# AIRZAI_BASE_BD_REVC_Sheet2.net
KiCad netlist of a schematic drawn in Altium Designer
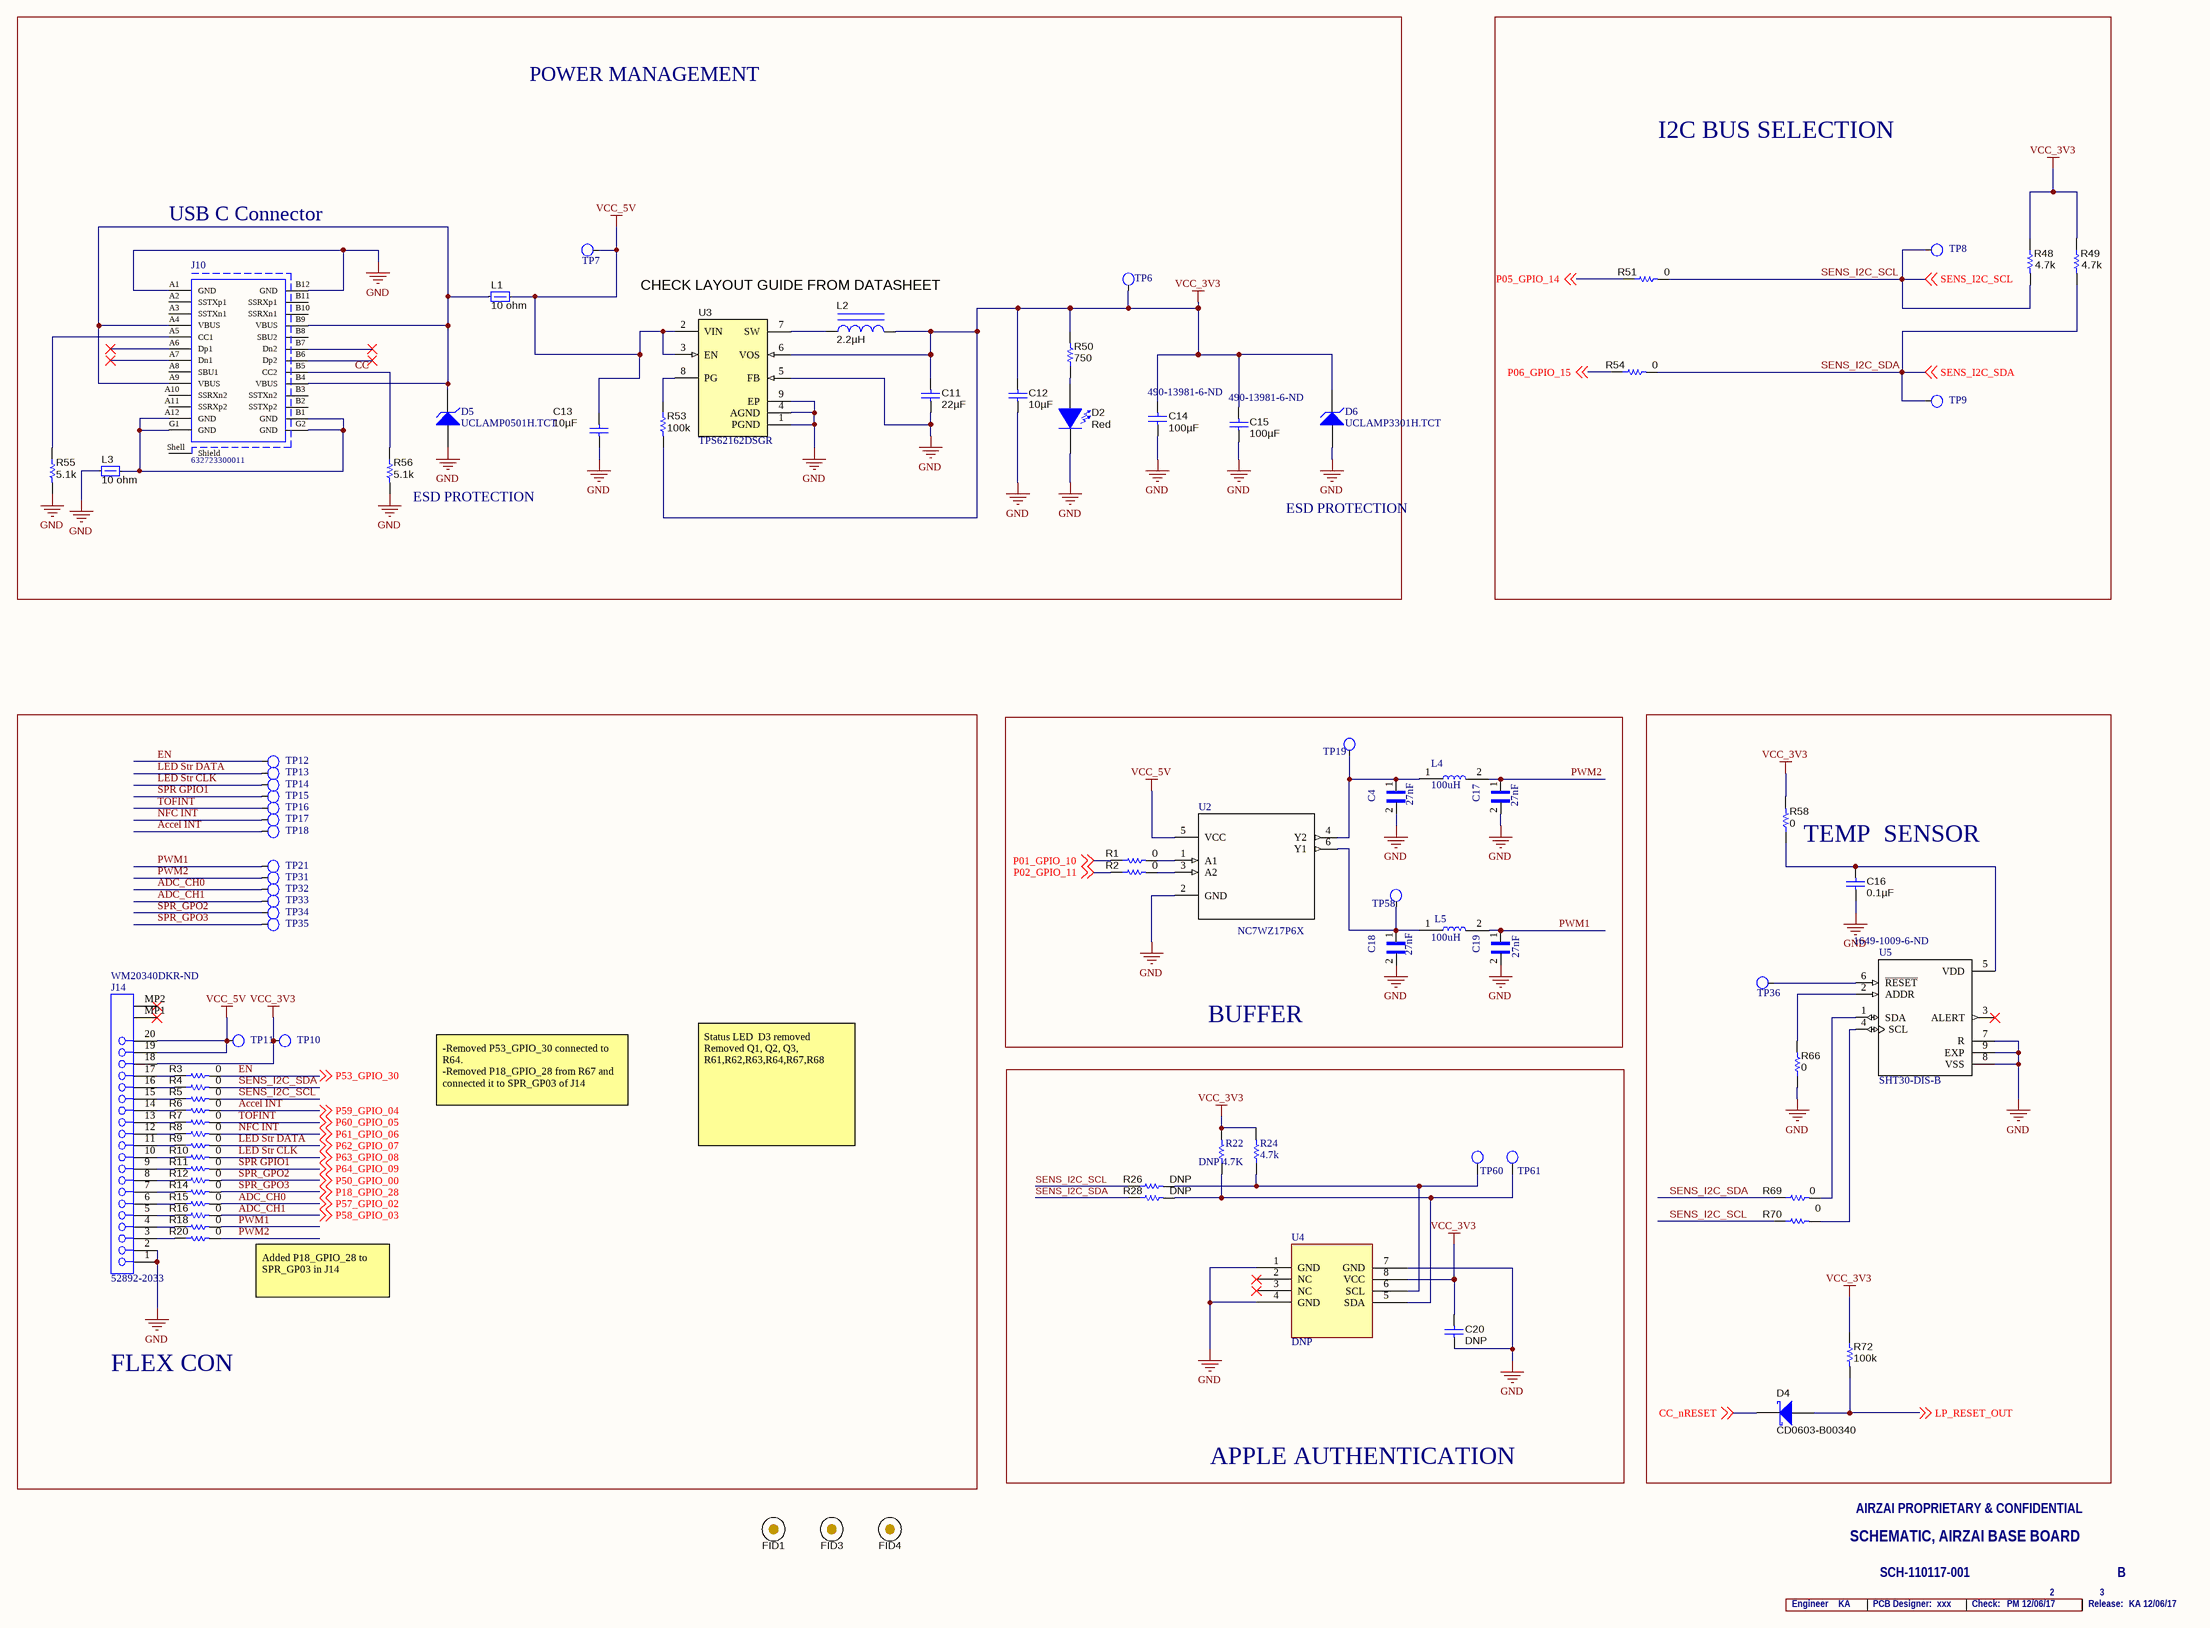
[diagram p0: AIRZAI_BASE_BD_REVC Sheet2.SchDoc]

(export (version "E")
  (design (tool "Eeschema 10.0.6"))
  (components
    (comp (ref "C4")
      (value "27nF")
      (footprint "1206CAP")
      (description "1206 27 nF 50 V Â±5% Tolerance C0G SMT Multilayer Ceramic Capacitor")
      (fields (field (name "MF") "Murata Electronics") (field (name "MP") "GRM3195C1H273JA01D"))
      (libsource (lib "GRM3195C1H273JA01D") (part "GRM3195C1H273JA01D"))
    )
    (comp (ref "C11")
      (value "C2012X5R1C226K125AC")
      (footprint "0805_HV")
      (description "CAP, CERM, 22 µF, 16 V, +/- 10%, X5R, 0805")
      (fields
        (field (name "VALUEDISPLAYED") "22µF")
        (field (name "MANUFACTURER") "TDK")
        (field (name "PUBLISHER") "Texas Instruments")
      )
      (libsource (lib "Capacitor_Ceramic") (part "C2012X5R1C226K125AC"))
    )
    (comp (ref "C12")
      (value "GRM21BR61A106KE19L")
      (footprint "0805_HV")
      (description "CAP, CERM, 10 µF, 10 V, +/- 10%, X5R, 0805")
      (fields
        (field (name "VALUEDISPLAYED") "10µF")
        (field (name "MANUFACTURER") "MuRata")
        (field (name "PUBLISHER") "Texas Instruments")
      )
      (libsource (lib "Capacitor_Ceramic") (part "GRM21BR61A106KE19L"))
    )
    (comp (ref "C13")
      (value "GRM21BR61A106KE19L")
      (footprint "0805_HV")
      (description "CAP, CERM, 10 µF, 10 V, +/- 10%, X5R, 0805")
      (fields
        (field (name "VALUEDISPLAYED") "10µF")
        (field (name "MANUFACTURER") "MuRata")
        (field (name "PUBLISHER") "Texas Instruments")
      )
      (libsource (lib "Capacitor_Ceramic") (part "GRM21BR61A106KE19L"))
    )
    (comp (ref "C14")
      (value "GRM31CR60J107ME39L")
      (footprint "1206_180")
      (description "CAP, CERM, 100 µF, 6.3 V, +/- 20%, X5R, 1206")
      (fields
        (field (name "VALUEDISPLAYED") "100µF")
        (field (name "MANUFACTURER") "MuRata")
        (field (name "SUPPLIER PART NUMBER 3") "490-13981-6-ND")
        (field (name "PUBLISHER") "Texas Instruments")
      )
      (libsource (lib "Capacitor_Ceramic") (part "GRM31CR60J107ME39L"))
    )
    (comp (ref "C15")
      (value "GRM31CR60J107ME39L")
      (footprint "1206_180")
      (description "CAP, CERM, 100 µF, 6.3 V, +/- 20%, X5R, 1206")
      (fields
        (field (name "VALUEDISPLAYED") "100µF")
        (field (name "MANUFACTURER") "MuRata")
        (field (name "SUPPLIER PART NUMBER 3") "490-13981-6-ND")
        (field (name "PUBLISHER") "Texas Instruments")
      )
      (libsource (lib "Capacitor_Ceramic") (part "GRM31CR60J107ME39L"))
    )
    (comp (ref "C16")
      (value "GRM155R61A104KA01D")
      (footprint "0402")
      (description "CAP, CERM, 0.1 µF, 10 V, +/- 10%, X5R, 0402")
      (fields
        (field (name "VALUEDISPLAYED") "0.1µF")
        (field (name "MANUFACTURER") "MuRata")
        (field (name "PUBLISHER") "Texas Instruments")
      )
      (libsource (lib "Capacitor_Ceramic") (part "GRM155R61A104KA01D"))
    )
    (comp (ref "C17")
      (value "27nF")
      (footprint "1206CAP")
      (description "1206 27 nF 50 V Â±5% Tolerance C0G SMT Multilayer Ceramic Capacitor")
      (fields (field (name "MF") "Murata Electronics") (field (name "MP") "GRM3195C1H273JA01D"))
      (libsource (lib "GRM3195C1H273JA01D") (part "GRM3195C1H273JA01D"))
    )
    (comp (ref "C18")
      (value "27nF")
      (footprint "1206CAP")
      (description "1206 27 nF 50 V Â±5% Tolerance C0G SMT Multilayer Ceramic Capacitor")
      (fields (field (name "MF") "Murata Electronics") (field (name "MP") "GRM3195C1H273JA01D"))
      (libsource (lib "GRM3195C1H273JA01D") (part "GRM3195C1H273JA01D"))
    )
    (comp (ref "C19")
      (value "27nF")
      (footprint "1206CAP")
      (description "1206 27 nF 50 V Â±5% Tolerance C0G SMT Multilayer Ceramic Capacitor")
      (fields (field (name "MF") "Murata Electronics") (field (name "MP") "GRM3195C1H273JA01D"))
      (libsource (lib "GRM3195C1H273JA01D") (part "GRM3195C1H273JA01D"))
    )
    (comp (ref "C20")
      (value "C1005X5R1A104K050BA")
      (footprint "SM0402_BTD.1SM_ACT_H55_CAP_WSS")
      (description "CAP, CERM, 0.1 µF, 10 V, +/- 10%, X5R, 0402")
      (fields
        (field (name "MANUFACTURER") "TDK")
        (field (name "VALUEDISPLAYED") "DNP")
        (field (name "PUBLISHER") "Texas Instruments")
      )
      (libsource (lib "AIRZAI_MBD_REVB2") (part "C1005X5R1A104K050BA"))
    )
    (comp (ref "D2")
      (value "Red")
      (footprint "SML-31_Red")
      (description "LED, Red, SMD")
      (fields
        (field (name "MANUFACTURER") "Rohm")
        (field (name "PARTNUMBER") "SML-311UTT86")
        (field (name "PUBLISHER") "Texas Instruments")
      )
      (libsource (lib "LED") (part "SML-311UTT86"))
    )
    (comp (ref "D4")
      (value "CD0603-B00340")
      (footprint "Diode_0603")
      (description "Diode, Schottky, 45 V, 0.03 A, 0603 Diode")
      (fields (field (name "MANUFACTURER") "Bourns") (field (name "PUBLISHER") "Texas Instruments"))
      (libsource (lib "Diode") (part "CD0603-B00340"))
    )
    (comp (ref "D5")
      (value "UCLAMP0501H.TCT")
      (footprint "SOD-523")
      (description "TVS DIODE 5V 12.5V SOD523")
      (fields (field (name "MANUFACTURER") "Semtech"))
      (libsource (lib "AIRZAI_BASE_BD_REVA") (part "UCLAMP0501H.TCT"))
    )
    (comp (ref "D6")
      (value "UCLAMP3301H.TCT")
      (footprint "SOD-523")
      (description "TVS DIODE 3.3V 8V SOD523")
      (fields (field (name "MANUFACTURER") "Semtech"))
      (libsource (lib "AIRZAI_BASE_BD_REVA") (part "UCLAMP3301H.TCT"))
    )
    (comp (ref "FID1")
      (value "Fiducial")
      (footprint "Fiducial10-20")
      (description "Fiducial mark.  There is nothing to buy or mount.")
      (fields (field (name "SYMBOLCREATOR") "codlsc") (field (name "PUBLISHER") "Texas Instruments"))
      (libsource (lib "MiscParts") (part "Fiducial"))
    )
    (comp (ref "FID3")
      (value "Fiducial")
      (footprint "Fiducial10-20")
      (description "Fiducial mark.  There is nothing to buy or mount.")
      (fields (field (name "SYMBOLCREATOR") "codlsc") (field (name "PUBLISHER") "Texas Instruments"))
      (libsource (lib "MiscParts") (part "Fiducial"))
    )
    (comp (ref "FID4")
      (value "Fiducial")
      (footprint "Fiducial10-20")
      (description "Fiducial mark.  There is nothing to buy or mount.")
      (fields (field (name "SYMBOLCREATOR") "codlsc") (field (name "PUBLISHER") "Texas Instruments"))
      (libsource (lib "MiscParts") (part "Fiducial"))
    )
    (comp (ref "J10")
      (value "632723300011")
      (footprint "632723300011")
      (description "USB 3.1 Type C Receptacle WR-COM, Horizontal, SMT / THT")
      (fields (field (name "PUBLISHER") "Wurth Elektronik"))
      (libsource (lib "Altium_WR-COM_USB-Connectors (rev18b)") (part "632723300011"))
    )
    (comp (ref "J14")
      (value "52892-2033")
      (footprint "MOLX-52892-2033")
      (fields (field (name "MANUFACTURER") "Molex") (field (name "SUPPLIER PART NUMBER 1") "WM20340DKR-ND"))
      (libsource (lib "Altium Content Vault") (part "MOLX-52892-2033"))
    )
    (comp (ref "L1")
      (value "10 ohm")
      (footprint "0402")
      (description "Ferrite Bead, 10 ohm @ 100 MHz, 1 A, 0402")
      (fields
        (field (name "PARTNUMBER") "BLM15AG100SN1D")
        (field (name "MANUFACTURER") "MuRata")
        (field (name "PUBLISHER") "Texas Instruments")
      )
      (libsource (lib "") (part "BLM15AG100SN1D_1"))
    )
    (comp (ref "L2")
      (value "BRC2012T2R2MD")
      (footprint "0805_HV")
      (description "Inductor, Wirewound, 2.2 µH, 1 A, 0.143 ohm, SMD")
      (fields
        (field (name "VALUEDISPLAYED") "2.2µH")
        (field (name "MANUFACTURER") "Taiyo Yuden")
        (field (name "PUBLISHER") "Texas Instruments")
      )
      (libsource (lib "Inductor_Other") (part "BRC2012T2R2MD"))
    )
    (comp (ref "L3")
      (value "10 ohm")
      (footprint "0402")
      (description "Ferrite Bead, 10 ohm @ 100 MHz, 1 A, 0402")
      (fields
        (field (name "PARTNUMBER") "BLM15AG100SN1D")
        (field (name "MANUFACTURER") "MuRata")
        (field (name "PUBLISHER") "Texas Instruments")
      )
      (libsource (lib "FerriteBead") (part "BLM15AG100SN1D"))
    )
    (comp (ref "L4")
      (value "100uH")
      (footprint "0805_Inductor")
      (description "Fixed Ind 100uh 2ma 3.1 Ohm Smd")
      (fields (field (name "MP") "MLF2012C101KTD25") (field (name "MF") "TDK"))
      (libsource (lib "MLF2012C101KTD25") (part "MLF2012C101KTD25"))
    )
    (comp (ref "L5")
      (value "100uH")
      (footprint "0805_Inductor")
      (description "Fixed Ind 100uh 2ma 3.1 Ohm Smd")
      (fields (field (name "MP") "MLF2012C101KTD25") (field (name "MF") "TDK"))
      (libsource (lib "MLF2012C101KTD25") (part "MLF2012C101KTD25"))
    )
    (comp (ref "R1")
      (value "ERJ-2GE0R00X")
      (footprint "0402")
      (description "RES, 0, 5%, 0.063 W, 0402")
      (fields
        (field (name "VALUEDISPLAYED") "0")
        (field (name "MANUFACTURER") "Panasonic")
        (field (name "DIGI-KEY_PART_NUMBER") "P0.0JCT-ND")
        (field (name "PUBLISHER") "Texas Instruments")
      )
      (libsource (lib "Resistor_0402") (part "ERJ-2GE0R00X"))
    )
    (comp (ref "R2")
      (value "ERJ-2GE0R00X")
      (footprint "0402")
      (description "RES, 0, 5%, 0.063 W, 0402")
      (fields
        (field (name "VALUEDISPLAYED") "0")
        (field (name "MANUFACTURER") "Panasonic")
        (field (name "DIGI-KEY_PART_NUMBER") "P0.0JCT-ND")
        (field (name "PUBLISHER") "Texas Instruments")
      )
      (libsource (lib "Resistor_0402") (part "ERJ-2GE0R00X"))
    )
    (comp (ref "R3")
      (value "ERJ-2GE0R00X")
      (footprint "0402")
      (description "RES, 0, 5%, 0.063 W, 0402")
      (fields
        (field (name "VALUEDISPLAYED") "0")
        (field (name "MANUFACTURER") "Panasonic")
        (field (name "PUBLISHER") "Texas Instruments")
      )
      (libsource (lib "Resistor_0402") (part "ERJ-2GE0R00X"))
    )
    (comp (ref "R4")
      (value "ERJ-2GE0R00X")
      (footprint "0402")
      (description "RES, 0, 5%, 0.063 W, 0402")
      (fields
        (field (name "VALUEDISPLAYED") "0")
        (field (name "MANUFACTURER") "Panasonic")
        (field (name "PUBLISHER") "Texas Instruments")
      )
      (libsource (lib "Resistor_0402") (part "ERJ-2GE0R00X"))
    )
    (comp (ref "R5")
      (value "ERJ-2GE0R00X")
      (footprint "0402")
      (description "RES, 0, 5%, 0.063 W, 0402")
      (fields
        (field (name "VALUEDISPLAYED") "0")
        (field (name "MANUFACTURER") "Panasonic")
        (field (name "PUBLISHER") "Texas Instruments")
      )
      (libsource (lib "Resistor_0402") (part "ERJ-2GE0R00X"))
    )
    (comp (ref "R6")
      (value "ERJ-2GE0R00X")
      (footprint "0402")
      (description "RES, 0, 5%, 0.063 W, 0402")
      (fields
        (field (name "VALUEDISPLAYED") "0")
        (field (name "MANUFACTURER") "Panasonic")
        (field (name "PUBLISHER") "Texas Instruments")
      )
      (libsource (lib "Resistor_0402") (part "ERJ-2GE0R00X"))
    )
    (comp (ref "R7")
      (value "ERJ-2GE0R00X")
      (footprint "0402")
      (description "RES, 0, 5%, 0.063 W, 0402")
      (fields
        (field (name "VALUEDISPLAYED") "0")
        (field (name "MANUFACTURER") "Panasonic")
        (field (name "PUBLISHER") "Texas Instruments")
      )
      (libsource (lib "Resistor_0402") (part "ERJ-2GE0R00X"))
    )
    (comp (ref "R8")
      (value "ERJ-2GE0R00X")
      (footprint "0402")
      (description "RES, 0, 5%, 0.063 W, 0402")
      (fields
        (field (name "VALUEDISPLAYED") "0")
        (field (name "MANUFACTURER") "Panasonic")
        (field (name "PUBLISHER") "Texas Instruments")
      )
      (libsource (lib "Resistor_0402") (part "ERJ-2GE0R00X"))
    )
    (comp (ref "R9")
      (value "ERJ-2GE0R00X")
      (footprint "0402")
      (description "RES, 0, 5%, 0.063 W, 0402")
      (fields
        (field (name "VALUEDISPLAYED") "0")
        (field (name "MANUFACTURER") "Panasonic")
        (field (name "PUBLISHER") "Texas Instruments")
      )
      (libsource (lib "Resistor_0402") (part "ERJ-2GE0R00X"))
    )
    (comp (ref "R10")
      (value "ERJ-2GE0R00X")
      (footprint "0402")
      (description "RES, 0, 5%, 0.063 W, 0402")
      (fields
        (field (name "VALUEDISPLAYED") "0")
        (field (name "MANUFACTURER") "Panasonic")
        (field (name "PUBLISHER") "Texas Instruments")
      )
      (libsource (lib "Resistor_0402") (part "ERJ-2GE0R00X"))
    )
    (comp (ref "R11")
      (value "ERJ-2GE0R00X")
      (footprint "0402")
      (description "RES, 0, 5%, 0.063 W, 0402")
      (fields
        (field (name "VALUEDISPLAYED") "0")
        (field (name "MANUFACTURER") "Panasonic")
        (field (name "PUBLISHER") "Texas Instruments")
      )
      (libsource (lib "Resistor_0402") (part "ERJ-2GE0R00X"))
    )
    (comp (ref "R12")
      (value "ERJ-2GE0R00X")
      (footprint "0402")
      (description "RES, 0, 5%, 0.063 W, 0402")
      (fields
        (field (name "VALUEDISPLAYED") "0")
        (field (name "MANUFACTURER") "Panasonic")
        (field (name "PUBLISHER") "Texas Instruments")
      )
      (libsource (lib "Resistor_0402") (part "ERJ-2GE0R00X"))
    )
    (comp (ref "R14")
      (value "ERJ-2GE0R00X")
      (footprint "0402")
      (description "RES, 0, 5%, 0.063 W, 0402")
      (fields
        (field (name "VALUEDISPLAYED") "0")
        (field (name "MANUFACTURER") "Panasonic")
        (field (name "PUBLISHER") "Texas Instruments")
      )
      (libsource (lib "Resistor_0402") (part "ERJ-2GE0R00X"))
    )
    (comp (ref "R15")
      (value "ERJ-2GE0R00X")
      (footprint "0402")
      (description "RES, 0, 5%, 0.063 W, 0402")
      (fields
        (field (name "VALUEDISPLAYED") "0")
        (field (name "MANUFACTURER") "Panasonic")
        (field (name "PUBLISHER") "Texas Instruments")
      )
      (libsource (lib "Resistor_0402") (part "ERJ-2GE0R00X"))
    )
    (comp (ref "R16")
      (value "ERJ-2GE0R00X")
      (footprint "0402")
      (description "RES, 0, 5%, 0.063 W, 0402")
      (fields
        (field (name "VALUEDISPLAYED") "0")
        (field (name "MANUFACTURER") "Panasonic")
        (field (name "PUBLISHER") "Texas Instruments")
      )
      (libsource (lib "Resistor_0402") (part "ERJ-2GE0R00X"))
    )
    (comp (ref "R18")
      (value "ERJ-2GE0R00X")
      (footprint "0402")
      (description "RES, 0, 5%, 0.063 W, 0402")
      (fields
        (field (name "VALUEDISPLAYED") "0")
        (field (name "MANUFACTURER") "Panasonic")
        (field (name "PUBLISHER") "Texas Instruments")
      )
      (libsource (lib "Resistor_0402") (part "ERJ-2GE0R00X"))
    )
    (comp (ref "R20")
      (value "ERJ-2GE0R00X")
      (footprint "0402")
      (description "RES, 0, 5%, 0.063 W, 0402")
      (fields
        (field (name "VALUEDISPLAYED") "0")
        (field (name "MANUFACTURER") "Panasonic")
        (field (name "PUBLISHER") "Texas Instruments")
      )
      (libsource (lib "Resistor_0402") (part "ERJ-2GE0R00X"))
    )
    (comp (ref "R22")
      (value "RMCF0402JT4K70")
      (footprint "0402")
      (description "Chip Resistor, 4.7 KOhm, +/- 5%, 0.063 W, -55 to 155 degC, 0402 (1005 Metric), RoHS, Tape and Reel")
      (fields
        (field (name "MANUFACTURER") "Stackpole-Electronics-Inc.")
        (field (name "TOLERANCE") "±5%")
        (field (name "RESISTANCE (OHMS)") "DNP 4.7K")
      )
      (libsource (lib "AIRZAI_BASE_BD_REVA") (part "RES-2"))
    )
    (comp (ref "R24")
      (value "RMCF0402JT4K70")
      (footprint "0402")
      (description "Chip Resistor, 4.7 KOhm, +/- 5%, 0.063 W, -55 to 155 degC, 0402 (1005 Metric), RoHS, Tape and Reel")
      (fields
        (field (name "MANUFACTURER") "Stackpole-Electronics-Inc.")
        (field (name "TOLERANCE") "±5%")
        (field (name "RESISTANCE (OHMS)") "4.7k")
      )
      (libsource (lib "AIRZAI_BASE_BD_REVA") (part "RES-2"))
    )
    (comp (ref "R26")
      (value "ERJ-2GE0R00X")
      (footprint "0402")
      (description "RES, 0, 5%, 0.063 W, 0402")
      (fields
        (field (name "VALUEDISPLAYED") "DNP")
        (field (name "MANUFACTURER") "Panasonic")
        (field (name "DIGI-KEY_PART_NUMBER") "P0.0JCT-ND")
        (field (name "PUBLISHER") "Texas Instruments")
      )
      (libsource (lib "Resistor_0402") (part "ERJ-2GE0R00X"))
    )
    (comp (ref "R28")
      (value "ERJ-2GE0R00X")
      (footprint "0402")
      (description "RES, 0, 5%, 0.063 W, 0402")
      (fields
        (field (name "VALUEDISPLAYED") "DNP")
        (field (name "MANUFACTURER") "Panasonic")
        (field (name "DIGI-KEY_PART_NUMBER") "P0.0JCT-ND")
        (field (name "PUBLISHER") "Texas Instruments")
      )
      (libsource (lib "Resistor_0402") (part "ERJ-2GE0R00X"))
    )
    (comp (ref "R48")
      (value "4.7k")
      (footprint "0402")
      (description "RES SMD 4.7K OHM 1% 1/16W 0402")
      (fields
        (field (name "MANUFACTURER") "Yageo")
        (field (name "MANUFACTURER PART NUMBER") "RC0402FR-074K7L")
      )
      (libsource (lib "Resistor_0402") (part "CRCW04023K30JNED"))
    )
    (comp (ref "R49")
      (value "4.7k")
      (footprint "0402")
      (description "RES SMD 4.7K OHM 1% 1/16W 0402")
      (fields
        (field (name "MANUFACTURER") "Yageo")
        (field (name "MANUFACTURER PART NUMBER") "RC0402FR-074K7L")
      )
      (libsource (lib "Resistor_0402") (part "CRCW04023K30JNED"))
    )
    (comp (ref "R50")
      (value "RC0603JR-07750RL")
      (footprint "0603")
      (description "RES, 750, 5%, 0.1 W, 0603")
      (fields
        (field (name "VALUEDISPLAYED") "750")
        (field (name "MANUFACTURER") "Yageo America")
        (field (name "PUBLISHER") "Texas Instruments")
      )
      (libsource (lib "Resistor_0603") (part "RC0603JR-07750RL"))
    )
    (comp (ref "R51")
      (value "ERJ-2GE0R00X")
      (footprint "0402")
      (description "RES, 0, 5%, 0.063 W, 0402")
      (fields
        (field (name "VALUEDISPLAYED") "0")
        (field (name "MANUFACTURER") "Panasonic")
        (field (name "PUBLISHER") "Texas Instruments")
      )
      (libsource (lib "Resistor_0402") (part "ERJ-2GE0R00X"))
    )
    (comp (ref "R53")
      (value "CRCW0402100KJNED")
      (footprint "0402")
      (description "RES, 100 k, 5%, 0.063 W, 0402")
      (fields
        (field (name "VALUEDISPLAYED") "100k")
        (field (name "MANUFACTURER") "Vishay-Dale")
        (field (name "PUBLISHER") "Texas Instruments")
      )
      (libsource (lib "Resistor_0402") (part "CRCW0402100KJNED"))
    )
    (comp (ref "R54")
      (value "ERJ-2GE0R00X")
      (footprint "0402")
      (description "RES, 0, 5%, 0.063 W, 0402")
      (fields
        (field (name "VALUEDISPLAYED") "0")
        (field (name "MANUFACTURER") "Panasonic")
        (field (name "PUBLISHER") "Texas Instruments")
      )
      (libsource (lib "Resistor_0402") (part "ERJ-2GE0R00X"))
    )
    (comp (ref "R55")
      (value "CRCW040210K0JNED")
      (footprint "0402")
      (description "RES, 10 k, 5%, 0.063 W, 0402")
      (fields
        (field (name "VALUEDISPLAYED") "5.1k")
        (field (name "MANUFACTURER") "Vishay-Dale")
        (field (name "PUBLISHER") "Texas Instruments")
      )
      (libsource (lib "Resistor_0402") (part "CRCW040210K0JNED"))
    )
    (comp (ref "R56")
      (value "CRCW040210K0JNED")
      (footprint "0402")
      (description "RES, 10 k, 5%, 0.063 W, 0402")
      (fields
        (field (name "VALUEDISPLAYED") "5.1k")
        (field (name "MANUFACTURER") "Vishay-Dale")
        (field (name "PUBLISHER") "Texas Instruments")
      )
      (libsource (lib "Resistor_0402") (part "CRCW040210K0JNED"))
    )
    (comp (ref "R58")
      (value "ERJ-2GE0R00X")
      (footprint "0402")
      (description "RES, 0, 5%, 0.063 W, 0402")
      (fields
        (field (name "VALUEDISPLAYED") "0")
        (field (name "MANUFACTURER") "Panasonic")
        (field (name "PUBLISHER") "Texas Instruments")
      )
      (libsource (lib "Resistor_0402") (part "ERJ-2GE0R00X"))
    )
    (comp (ref "R66")
      (value "ERJ-2GE0R00X")
      (footprint "0402")
      (description "RES, 0, 5%, 0.063 W, 0402")
      (fields
        (field (name "VALUEDISPLAYED") "0")
        (field (name "MANUFACTURER") "Panasonic")
        (field (name "PUBLISHER") "Texas Instruments")
      )
      (libsource (lib "Resistor_0402") (part "ERJ-2GE0R00X"))
    )
    (comp (ref "R69")
      (value "ERJ-2GE0R00X")
      (footprint "0402")
      (description "RES, 0, 5%, 0.063 W, 0402")
      (fields
        (field (name "VALUEDISPLAYED") "0")
        (field (name "MANUFACTURER") "Panasonic")
        (field (name "PUBLISHER") "Texas Instruments")
      )
      (libsource (lib "Resistor_0402") (part "ERJ-2GE0R00X"))
    )
    (comp (ref "R70")
      (value "ERJ-2GE0R00X")
      (footprint "0402")
      (description "RES, 0, 5%, 0.063 W, 0402")
      (fields
        (field (name "VALUEDISPLAYED") "0")
        (field (name "MANUFACTURER") "Panasonic")
        (field (name "PUBLISHER") "Texas Instruments")
      )
      (libsource (lib "Resistor_0402") (part "ERJ-2GE0R00X"))
    )
    (comp (ref "R72")
      (value "CRCW0402100KJNED")
      (footprint "0402")
      (description "RES, 100 k, 5%, 0.063 W, 0402")
      (fields
        (field (name "VALUEDISPLAYED") "100k")
        (field (name "MANUFACTURER") "Vishay-Dale")
        (field (name "PUBLISHER") "Texas Instruments")
      )
      (libsource (lib "Resistor_0402") (part "CRCW0402100KJNED"))
    )
    (comp (ref "TP6")
      (value "WIREPT")
      (footprint "TP_0.9MM")
      (libsource (lib "EAGLE_CAD_Library") (part "WIREPT"))
    )
    (comp (ref "TP7")
      (value "WIREPT")
      (footprint "TP_0.9MM")
      (libsource (lib "EAGLE_CAD_Library") (part "WIREPT"))
    )
    (comp (ref "TP8")
      (value "WIREPT")
      (footprint "TP_0.9MM")
      (libsource (lib "EAGLE_CAD_Library") (part "WIREPT"))
    )
    (comp (ref "TP9")
      (value "WIREPT")
      (footprint "TP_0.9MM")
      (libsource (lib "EAGLE_CAD_Library") (part "WIREPT"))
    )
    (comp (ref "TP10")
      (value "WIREPT")
      (footprint "TP_0.9MM")
      (libsource (lib "EAGLE_CAD_Library") (part "WIREPT"))
    )
    (comp (ref "TP11")
      (value "WIREPT")
      (footprint "TP_0.9MM")
      (libsource (lib "EAGLE_CAD_Library") (part "WIREPT"))
    )
    (comp (ref "TP12")
      (value "WIREPT")
      (footprint "TP_0.9MM")
      (libsource (lib "EAGLE_CAD_Library") (part "WIREPT"))
    )
    (comp (ref "TP13")
      (value "WIREPT")
      (footprint "TP_0.9MM")
      (libsource (lib "EAGLE_CAD_Library") (part "WIREPT"))
    )
    (comp (ref "TP14")
      (value "WIREPT")
      (footprint "TP_0.9MM")
      (libsource (lib "EAGLE_CAD_Library") (part "WIREPT"))
    )
    (comp (ref "TP15")
      (value "WIREPT")
      (footprint "TP_0.9MM")
      (libsource (lib "EAGLE_CAD_Library") (part "WIREPT"))
    )
    (comp (ref "TP16")
      (value "WIREPT")
      (footprint "TP_0.9MM")
      (libsource (lib "EAGLE_CAD_Library") (part "WIREPT"))
    )
    (comp (ref "TP17")
      (value "WIREPT")
      (footprint "TP_0.9MM")
      (libsource (lib "EAGLE_CAD_Library") (part "WIREPT"))
    )
    (comp (ref "TP18")
      (value "WIREPT")
      (footprint "TP_0.9MM")
      (libsource (lib "EAGLE_CAD_Library") (part "WIREPT"))
    )
    (comp (ref "TP19")
      (value "WIREPT")
      (footprint "TP_0.9MM")
      (libsource (lib "AIRZAI_MBD_REVB") (part "WIREPT"))
    )
    (comp (ref "TP21")
      (value "WIREPT")
      (footprint "TP_0.9MM")
      (libsource (lib "EAGLE_CAD_Library") (part "WIREPT"))
    )
    (comp (ref "TP31")
      (value "WIREPT")
      (footprint "TP_0.9MM")
      (libsource (lib "EAGLE_CAD_Library") (part "WIREPT"))
    )
    (comp (ref "TP32")
      (value "WIREPT")
      (footprint "TP_0.9MM")
      (libsource (lib "EAGLE_CAD_Library") (part "WIREPT"))
    )
    (comp (ref "TP33")
      (value "WIREPT")
      (footprint "TP_0.9MM")
      (libsource (lib "EAGLE_CAD_Library") (part "WIREPT"))
    )
    (comp (ref "TP34")
      (value "WIREPT")
      (footprint "TP_0.9MM")
      (libsource (lib "EAGLE_CAD_Library") (part "WIREPT"))
    )
    (comp (ref "TP35")
      (value "WIREPT")
      (footprint "TP_0.9MM")
      (libsource (lib "EAGLE_CAD_Library") (part "WIREPT"))
    )
    (comp (ref "TP36")
      (value "WIREPT")
      (footprint "TP_0.9MM")
      (libsource (lib "EAGLE_CAD_Library") (part "WIREPT"))
    )
    (comp (ref "TP58")
      (value "WIREPT")
      (footprint "TP_0.9MM")
      (libsource (lib "AIRZAI_MBD_REVB") (part "WIREPT"))
    )
    (comp (ref "TP60")
      (value "TESTPOINT")
      (footprint "TP_0.9MM")
      (libsource (lib "AIRZAI_LID_BD_REVA") (part "TESTPOINT"))
    )
    (comp (ref "TP61")
      (value "TESTPOINT")
      (footprint "TP_0.9MM")
      (libsource (lib "AIRZAI_LID_BD_REVA") (part "TESTPOINT"))
    )
    (comp (ref "U2")
      (value "NC7WZ17P6X")
      (footprint "SC-70-NC7WZ17P6X")
      (description "NC7WZ17 Series 5.5 V TinyLogic UHS Dual Buffer w/ Schmitt Trigger Inputs-SC-70-6")
      (fields (field (name "MF") "ON Semiconductor"))
      (libsource (lib "NC7WZ17P6X") (part "NC7WZ17P6X"))
    )
    (comp (ref "U3")
      (value "TPS62162DSGR")
      (footprint "DSG0008A")
      (fields
        (field (name "MANUFACTURER") "Texas Instruments")
        (field (name "ALTERNATE PARTNUMBER") "Equivalent")
      )
      (libsource (lib "TI Power Management Step-Down Regulator") (part "TPS62162DSGR"))
    )
    (comp (ref "U4")
      (value "DNP")
      (footprint "XDFN-8P-Apple")
      (description "Auth 3.0 CP")
      (fields (field (name "MP") "MFI343S00177") (field (name "MF") "Apple"))
      (libsource (lib "MFI337S3959") (part "Apple CP"))
    )
    (comp (ref "U5")
      (value "SHT30-DIS-B")
      (footprint "DFN250X250X100-9N")
      (description "SHT3x Series 5.5 V Â±3 %RH 0 to 100% Temperature and Humidity Sensor - DFN-8")
      (fields (field (name "MF") "Sensirion AG") (field (name "SUPPLIER PART NUMBER 1") "1649-1009-6-ND"))
      (libsource (lib "SHT30-DIS-B") (part "SHT30-DIS-B"))
    )
  )
  (nets
    (net (code "1") (name "/CC") (class "Default")
      (node (ref "J10") (pin "B5") (pinfunction "CC2_B5") (pintype "passive"))
      (node (ref "R56") (pin "1") (pinfunction "1_1") (pintype "passive"))
    )
    (net (code "2") (name "/PWM1") (class "Default")
      (node (ref "C19") (pin "1") (pinfunction "1_1") (pintype "passive"))
      (node (ref "L5") (pin "2") (pinfunction "2_2") (pintype "passive"))
      (node (ref "R18") (pin "2") (pinfunction "2_2") (pintype "passive"))
      (node (ref "TP21") (pin "1") (pinfunction "1_1") (pintype "passive"))
    )
    (net (code "3") (name "/PWM2") (class "Default")
      (node (ref "C17") (pin "1") (pinfunction "1_1") (pintype "passive"))
      (node (ref "L4") (pin "2") (pinfunction "2_2") (pintype "passive"))
      (node (ref "R20") (pin "2") (pinfunction "2_2") (pintype "passive"))
      (node (ref "TP31") (pin "1") (pinfunction "1_1") (pintype "passive"))
    )
    (net (code "4") (name "CC_nRESET") (class "Default")
      (node (ref "D4") (pin "1") (pinfunction "K_1") (pintype "passive"))
    )
    (net (code "5") (name "GND") (class "Default")
      (node (ref "C11") (pin "2") (pinfunction "2_2") (pintype "passive"))
      (node (ref "C12") (pin "2") (pinfunction "2_2") (pintype "passive"))
      (node (ref "C13") (pin "2") (pinfunction "2_2") (pintype "passive"))
      (node (ref "C14") (pin "2") (pinfunction "2_2") (pintype "passive"))
      (node (ref "C15") (pin "2") (pinfunction "2_2") (pintype "passive"))
      (node (ref "C16") (pin "2") (pinfunction "2_2") (pintype "passive"))
      (node (ref "C17") (pin "2") (pinfunction "2_2") (pintype "passive"))
      (node (ref "C18") (pin "2") (pinfunction "2_2") (pintype "passive"))
      (node (ref "C19") (pin "2") (pinfunction "2_2") (pintype "passive"))
      (node (ref "C20") (pin "2") (pinfunction "2_2") (pintype "passive"))
      (node (ref "C4") (pin "2") (pinfunction "2_2") (pintype "passive"))
      (node (ref "D2") (pin "1") (pinfunction "K_1") (pintype "passive"))
      (node (ref "D5") (pin "A") (pinfunction "A_A") (pintype "passive"))
      (node (ref "D6") (pin "A") (pinfunction "A_A") (pintype "passive"))
      (node (ref "J10") (pin "A1") (pinfunction "GND_A1") (pintype "passive"))
      (node (ref "J10") (pin "B12") (pinfunction "GND_B12") (pintype "passive"))
      (node (ref "J14") (pin "1") (pinfunction "1_1") (pintype "passive"))
      (node (ref "J14") (pin "2") (pinfunction "2_2") (pintype "passive"))
      (node (ref "L3") (pin "2") (pinfunction "2_2") (pintype "passive"))
      (node (ref "R55") (pin "2") (pinfunction "2_2") (pintype "passive"))
      (node (ref "R56") (pin "2") (pinfunction "2_2") (pintype "passive"))
      (node (ref "R66") (pin "1") (pinfunction "1_1") (pintype "passive"))
      (node (ref "U2") (pin "2") (pinfunction "GND_2") (pintype "passive"))
      (node (ref "U3") (pin "1") (pinfunction "PGND_1") (pintype "power_in"))
      (node (ref "U3") (pin "4") (pinfunction "AGND_4") (pintype "power_in"))
      (node (ref "U3") (pin "5") (pinfunction "FB_5") (pintype "input"))
      (node (ref "U3") (pin "9") (pinfunction "EP_9") (pintype "power_in"))
      (node (ref "U4") (pin "1") (pinfunction "GND_1") (pintype "passive"))
      (node (ref "U4") (pin "4") (pinfunction "GND_4") (pintype "passive"))
      (node (ref "U4") (pin "7") (pinfunction "GND_7") (pintype "passive"))
      (node (ref "U5") (pin "7") (pinfunction "R_7") (pintype "passive"))
      (node (ref "U5") (pin "8") (pinfunction "VSS_8") (pintype "passive"))
      (node (ref "U5") (pin "9") (pinfunction "EXP_9") (pintype "passive"))
    )
    (net (code "6") (name "LP_RESET_OUT") (class "Default")
      (node (ref "D4") (pin "2") (pinfunction "A_2") (pintype "passive"))
      (node (ref "R72") (pin "2") (pinfunction "2_2") (pintype "passive"))
    )
    (net (code "7") (name "Net-(D2-A)") (class "Default")
      (node (ref "D2") (pin "2") (pinfunction "A_2") (pintype "passive"))
      (node (ref "R50") (pin "1") (pinfunction "1_1") (pintype "passive"))
    )
    (net (code "8") (name "Net-(D5-PadK)") (class "Default")
      (node (ref "D5") (pin "K") (pinfunction "K_K") (pintype "passive"))
      (node (ref "J10") (pin "A4") (pinfunction "VBUS_A4") (pintype "passive"))
      (node (ref "J10") (pin "A9") (pinfunction "VBUS_A9") (pintype "passive"))
      (node (ref "J10") (pin "B4") (pinfunction "VBUS_B4") (pintype "passive"))
      (node (ref "J10") (pin "B9") (pinfunction "VBUS_B9") (pintype "passive"))
      (node (ref "L1") (pin "1") (pinfunction "1_1") (pintype "passive"))
    )
    (net (code "9") (name "Net-(J10-CC1)") (class "Default")
      (node (ref "J10") (pin "A5") (pinfunction "CC1_A5") (pintype "passive"))
      (node (ref "R55") (pin "1") (pinfunction "1_1") (pintype "passive"))
    )
    (net (code "10") (name "Net-(J10-GND-PadA12)") (class "Default")
      (node (ref "J10") (pin "A12") (pinfunction "GND_A12") (pintype "passive"))
      (node (ref "J10") (pin "B1") (pinfunction "GND_B1") (pintype "passive"))
      (node (ref "J10") (pin "G1") (pinfunction "GND_G1") (pintype "passive"))
      (node (ref "J10") (pin "G2") (pinfunction "GND_G2") (pintype "passive"))
      (node (ref "L3") (pin "1") (pinfunction "1_1") (pintype "passive"))
    )
    (net (code "11") (name "Net-(J14-Pad3)") (class "Default")
      (node (ref "J14") (pin "3") (pinfunction "3_3") (pintype "passive"))
      (node (ref "R20") (pin "1") (pinfunction "1_1") (pintype "passive"))
    )
    (net (code "12") (name "Net-(J14-Pad4)") (class "Default")
      (node (ref "J14") (pin "4") (pinfunction "4_4") (pintype "passive"))
      (node (ref "R18") (pin "1") (pinfunction "1_1") (pintype "passive"))
    )
    (net (code "13") (name "Net-(J14-Pad5)") (class "Default")
      (node (ref "J14") (pin "5") (pinfunction "5_5") (pintype "passive"))
      (node (ref "R16") (pin "1") (pinfunction "1_1") (pintype "passive"))
    )
    (net (code "14") (name "Net-(J14-Pad6)") (class "Default")
      (node (ref "J14") (pin "6") (pinfunction "6_6") (pintype "passive"))
      (node (ref "R15") (pin "1") (pinfunction "1_1") (pintype "passive"))
    )
    (net (code "15") (name "Net-(J14-Pad7)") (class "Default")
      (node (ref "J14") (pin "7") (pinfunction "7_7") (pintype "passive"))
      (node (ref "R14") (pin "1") (pinfunction "1_1") (pintype "passive"))
    )
    (net (code "16") (name "Net-(J14-Pad8)") (class "Default")
      (node (ref "J14") (pin "8") (pinfunction "8_8") (pintype "passive"))
      (node (ref "R12") (pin "1") (pinfunction "1_1") (pintype "passive"))
    )
    (net (code "17") (name "Net-(J14-Pad9)") (class "Default")
      (node (ref "J14") (pin "9") (pinfunction "9_9") (pintype "passive"))
      (node (ref "R11") (pin "1") (pinfunction "1_1") (pintype "passive"))
    )
    (net (code "18") (name "Net-(J14-Pad10)") (class "Default")
      (node (ref "J14") (pin "10") (pinfunction "10_10") (pintype "passive"))
      (node (ref "R10") (pin "1") (pinfunction "1_1") (pintype "passive"))
    )
    (net (code "19") (name "Net-(J14-Pad11)") (class "Default")
      (node (ref "J14") (pin "11") (pinfunction "11_11") (pintype "passive"))
      (node (ref "R9") (pin "1") (pinfunction "1_1") (pintype "passive"))
    )
    (net (code "20") (name "Net-(J14-Pad12)") (class "Default")
      (node (ref "J14") (pin "12") (pinfunction "12_12") (pintype "passive"))
      (node (ref "R8") (pin "1") (pinfunction "1_1") (pintype "passive"))
    )
    (net (code "21") (name "Net-(J14-Pad13)") (class "Default")
      (node (ref "J14") (pin "13") (pinfunction "13_13") (pintype "passive"))
      (node (ref "R7") (pin "1") (pinfunction "1_1") (pintype "passive"))
    )
    (net (code "22") (name "Net-(J14-Pad14)") (class "Default")
      (node (ref "J14") (pin "14") (pinfunction "14_14") (pintype "passive"))
      (node (ref "R6") (pin "1") (pinfunction "1_1") (pintype "passive"))
    )
    (net (code "23") (name "Net-(J14-Pad15)") (class "Default")
      (node (ref "J14") (pin "15") (pinfunction "15_15") (pintype "passive"))
      (node (ref "R5") (pin "1") (pinfunction "1_1") (pintype "passive"))
    )
    (net (code "24") (name "Net-(J14-Pad16)") (class "Default")
      (node (ref "J14") (pin "16") (pinfunction "16_16") (pintype "passive"))
      (node (ref "R4") (pin "1") (pinfunction "1_1") (pintype "passive"))
    )
    (net (code "25") (name "Net-(J14-Pad17)") (class "Default")
      (node (ref "J14") (pin "17") (pinfunction "17_17") (pintype "passive"))
      (node (ref "R3") (pin "1") (pinfunction "1_1") (pintype "passive"))
    )
    (net (code "26") (name "Net-(U2-A1)") (class "Default")
      (node (ref "R1") (pin "2") (pinfunction "2_2") (pintype "passive"))
      (node (ref "U2") (pin "1") (pinfunction "A1_1") (pintype "input"))
    )
    (net (code "27") (name "Net-(U2-A2)") (class "Default")
      (node (ref "R2") (pin "2") (pinfunction "2_2") (pintype "passive"))
      (node (ref "U2") (pin "3") (pinfunction "A2_3") (pintype "input"))
    )
    (net (code "28") (name "Net-(U2-Y1)") (class "Default")
      (node (ref "C18") (pin "1") (pinfunction "1_1") (pintype "passive"))
      (node (ref "L5") (pin "1") (pinfunction "1_1") (pintype "passive"))
      (node (ref "TP58") (pin "1") (pinfunction "1_1") (pintype "passive"))
      (node (ref "U2") (pin "6") (pinfunction "Y1_6") (pintype "output"))
    )
    (net (code "29") (name "Net-(U2-Y2)") (class "Default")
      (node (ref "C4") (pin "1") (pinfunction "1_1") (pintype "passive"))
      (node (ref "L4") (pin "1") (pinfunction "1_1") (pintype "passive"))
      (node (ref "TP19") (pin "1") (pinfunction "1_1") (pintype "passive"))
      (node (ref "U2") (pin "4") (pinfunction "Y2_4") (pintype "output"))
    )
    (net (code "30") (name "Net-(U3-PG)") (class "Default")
      (node (ref "R53") (pin "1") (pinfunction "1_1") (pintype "passive"))
      (node (ref "U3") (pin "8") (pinfunction "PG_8") (pintype "tri_state"))
    )
    (net (code "31") (name "Net-(U3-SW)") (class "Default")
      (node (ref "L2") (pin "1") (pinfunction "1_1") (pintype "passive"))
      (node (ref "U3") (pin "7") (pinfunction "SW_7") (pintype "power_in"))
    )
    (net (code "32") (name "Net-(U4-SCL)") (class "Default")
      (node (ref "R24") (pin "1") (pinfunction "1_1") (pintype "passive"))
      (node (ref "R26") (pin "2") (pinfunction "2_2") (pintype "passive"))
      (node (ref "TP60") (pin "1") (pinfunction "1_1") (pintype "passive"))
      (node (ref "U4") (pin "6") (pinfunction "SCL_6") (pintype "passive"))
    )
    (net (code "33") (name "Net-(U4-SDA)") (class "Default")
      (node (ref "R22") (pin "1") (pinfunction "1_1") (pintype "passive"))
      (node (ref "R28") (pin "2") (pinfunction "2_2") (pintype "passive"))
      (node (ref "TP61") (pin "1") (pinfunction "1_1") (pintype "passive"))
      (node (ref "U4") (pin "5") (pinfunction "SDA_5") (pintype "passive"))
    )
    (net (code "34") (name "Net-(U5-ADDR)") (class "Default")
      (node (ref "R66") (pin "2") (pinfunction "2_2") (pintype "passive"))
      (node (ref "U5") (pin "2") (pinfunction "ADDR_2") (pintype "input"))
    )
    (net (code "35") (name "Net-(U5-SCL)") (class "Default")
      (node (ref "R70") (pin "2") (pinfunction "2_2") (pintype "passive"))
      (node (ref "U5") (pin "4") (pinfunction "SCL_4") (pintype "bidirectional"))
    )
    (net (code "36") (name "Net-(U5-SDA)") (class "Default")
      (node (ref "R69") (pin "2") (pinfunction "2_2") (pintype "passive"))
      (node (ref "U5") (pin "1") (pinfunction "SDA_1") (pintype "bidirectional"))
    )
    (net (code "37") (name "Net-(U5-VDD)") (class "Default")
      (node (ref "C16") (pin "1") (pinfunction "1_1") (pintype "passive"))
      (node (ref "R58") (pin "1") (pinfunction "1_1") (pintype "passive"))
      (node (ref "U5") (pin "5") (pinfunction "VDD_5") (pintype "power_in"))
    )
    (net (code "38") (name "Net-(U5-~{RESET})") (class "Default")
      (node (ref "TP36") (pin "1") (pinfunction "1_1") (pintype "passive"))
      (node (ref "U5") (pin "6") (pinfunction "~{RESET}_6") (pintype "input"))
    )
    (net (code "39") (name "P01_GPIO_10") (class "Default")
      (node (ref "R1") (pin "1") (pinfunction "1_1") (pintype "passive"))
    )
    (net (code "40") (name "P02_GPIO_11") (class "Default")
      (node (ref "R2") (pin "1") (pinfunction "1_1") (pintype "passive"))
    )
    (net (code "41") (name "P05_GPIO_14") (class "Default")
      (node (ref "R51") (pin "1") (pinfunction "1_1") (pintype "passive"))
    )
    (net (code "42") (name "P06_GPIO_15") (class "Default")
      (node (ref "R54") (pin "1") (pinfunction "1_1") (pintype "passive"))
    )
    (net (code "43") (name "P18_GPIO_28") (class "Default")
      (node (ref "R14") (pin "2") (pinfunction "2_2") (pintype "passive"))
      (node (ref "TP35") (pin "1") (pinfunction "1_1") (pintype "passive"))
    )
    (net (code "44") (name "P50_GPIO_00") (class "Default")
      (node (ref "R12") (pin "2") (pinfunction "2_2") (pintype "passive"))
      (node (ref "TP34") (pin "1") (pinfunction "1_1") (pintype "passive"))
    )
    (net (code "45") (name "P53_GPIO_30") (class "Default")
      (node (ref "R3") (pin "2") (pinfunction "2_2") (pintype "passive"))
      (node (ref "TP12") (pin "1") (pinfunction "1_1") (pintype "passive"))
    )
    (net (code "46") (name "P57_GPIO_02") (class "Default")
      (node (ref "R15") (pin "2") (pinfunction "2_2") (pintype "passive"))
      (node (ref "TP32") (pin "1") (pinfunction "1_1") (pintype "passive"))
    )
    (net (code "47") (name "P58_GPIO_03") (class "Default")
      (node (ref "R16") (pin "2") (pinfunction "2_2") (pintype "passive"))
      (node (ref "TP33") (pin "1") (pinfunction "1_1") (pintype "passive"))
    )
    (net (code "48") (name "P59_GPIO_04") (class "Default")
      (node (ref "R6") (pin "2") (pinfunction "2_2") (pintype "passive"))
      (node (ref "TP18") (pin "1") (pinfunction "1_1") (pintype "passive"))
    )
    (net (code "49") (name "P60_GPIO_05") (class "Default")
      (node (ref "R7") (pin "2") (pinfunction "2_2") (pintype "passive"))
      (node (ref "TP16") (pin "1") (pinfunction "1_1") (pintype "passive"))
    )
    (net (code "50") (name "P61_GPIO_06") (class "Default")
      (node (ref "R8") (pin "2") (pinfunction "2_2") (pintype "passive"))
      (node (ref "TP17") (pin "1") (pinfunction "1_1") (pintype "passive"))
    )
    (net (code "51") (name "P62_GPIO_07") (class "Default")
      (node (ref "R9") (pin "2") (pinfunction "2_2") (pintype "passive"))
      (node (ref "TP13") (pin "1") (pinfunction "1_1") (pintype "passive"))
    )
    (net (code "52") (name "P63_GPIO_08") (class "Default")
      (node (ref "R10") (pin "2") (pinfunction "2_2") (pintype "passive"))
      (node (ref "TP14") (pin "1") (pinfunction "1_1") (pintype "passive"))
    )
    (net (code "53") (name "P64_GPIO_09") (class "Default")
      (node (ref "R11") (pin "2") (pinfunction "2_2") (pintype "passive"))
      (node (ref "TP15") (pin "1") (pinfunction "1_1") (pintype "passive"))
    )
    (net (code "54") (name "SENS_I2C_SCL") (class "Default")
      (node (ref "R26") (pin "1") (pinfunction "1_1") (pintype "passive"))
      (node (ref "R48") (pin "2") (pinfunction "2_2") (pintype "passive"))
      (node (ref "R5") (pin "2") (pinfunction "2_2") (pintype "passive"))
      (node (ref "R51") (pin "2") (pinfunction "2_2") (pintype "passive"))
      (node (ref "R70") (pin "1") (pinfunction "1_1") (pintype "passive"))
      (node (ref "TP8") (pin "1") (pinfunction "1_1") (pintype "passive"))
    )
    (net (code "55") (name "SENS_I2C_SDA") (class "Default")
      (node (ref "R28") (pin "1") (pinfunction "1_1") (pintype "passive"))
      (node (ref "R4") (pin "2") (pinfunction "2_2") (pintype "passive"))
      (node (ref "R49") (pin "2") (pinfunction "2_2") (pintype "passive"))
      (node (ref "R54") (pin "2") (pinfunction "2_2") (pintype "passive"))
      (node (ref "R69") (pin "1") (pinfunction "1_1") (pintype "passive"))
      (node (ref "TP9") (pin "1") (pinfunction "1_1") (pintype "passive"))
    )
    (net (code "56") (name "VCC_3V3") (class "Default")
      (node (ref "C11") (pin "1") (pinfunction "1_1") (pintype "passive"))
      (node (ref "C12") (pin "1") (pinfunction "1_1") (pintype "passive"))
      (node (ref "C14") (pin "1") (pinfunction "1_1") (pintype "passive"))
      (node (ref "C15") (pin "1") (pinfunction "1_1") (pintype "passive"))
      (node (ref "C20") (pin "1") (pinfunction "1_1") (pintype "passive"))
      (node (ref "D6") (pin "K") (pinfunction "K_K") (pintype "passive"))
      (node (ref "J14") (pin "18") (pinfunction "18_18") (pintype "passive"))
      (node (ref "L2") (pin "2") (pinfunction "2_2") (pintype "passive"))
      (node (ref "R22") (pin "2") (pinfunction "2_2") (pintype "passive"))
      (node (ref "R24") (pin "2") (pinfunction "2_2") (pintype "passive"))
      (node (ref "R48") (pin "1") (pinfunction "1_1") (pintype "passive"))
      (node (ref "R49") (pin "1") (pinfunction "1_1") (pintype "passive"))
      (node (ref "R50") (pin "2") (pinfunction "2_2") (pintype "passive"))
      (node (ref "R53") (pin "2") (pinfunction "2_2") (pintype "passive"))
      (node (ref "R58") (pin "2") (pinfunction "2_2") (pintype "passive"))
      (node (ref "R72") (pin "1") (pinfunction "1_1") (pintype "passive"))
      (node (ref "TP10") (pin "1") (pinfunction "1_1") (pintype "passive"))
      (node (ref "TP6") (pin "1") (pinfunction "1_1") (pintype "passive"))
      (node (ref "U3") (pin "6") (pinfunction "VOS_6") (pintype "input"))
      (node (ref "U4") (pin "8") (pinfunction "VCC_8") (pintype "passive"))
    )
    (net (code "57") (name "VCC_5V") (class "Default")
      (node (ref "C13") (pin "1") (pinfunction "1_1") (pintype "passive"))
      (node (ref "J14") (pin "19") (pinfunction "19_19") (pintype "passive"))
      (node (ref "J14") (pin "20") (pinfunction "20_20") (pintype "passive"))
      (node (ref "L1") (pin "2") (pinfunction "2_2") (pintype "passive"))
      (node (ref "TP11") (pin "1") (pinfunction "1_1") (pintype "passive"))
      (node (ref "TP7") (pin "1") (pinfunction "1_1") (pintype "passive"))
      (node (ref "U2") (pin "5") (pinfunction "VCC_5") (pintype "power_in"))
      (node (ref "U3") (pin "2") (pinfunction "VIN_2") (pintype "power_in"))
      (node (ref "U3") (pin "3") (pinfunction "EN_3") (pintype "input"))
    )
    (net (code "58") (name "unconnected-(J10-Dn1-PadA7)") (class "Default")
      (node (ref "J10") (pin "A7") (pinfunction "Dn1_A7") (pintype "passive+no_connect"))
    )
    (net (code "59") (name "unconnected-(J10-Dn2-PadB7)") (class "Default")
      (node (ref "J10") (pin "B7") (pinfunction "Dn2_B7") (pintype "passive+no_connect"))
    )
    (net (code "60") (name "unconnected-(J10-Dp1-PadA6)") (class "Default")
      (node (ref "J10") (pin "A6") (pinfunction "Dp1_A6") (pintype "passive+no_connect"))
    )
    (net (code "61") (name "unconnected-(J10-Dp2-PadB6)") (class "Default")
      (node (ref "J10") (pin "B6") (pinfunction "Dp2_B6") (pintype "passive+no_connect"))
    )
    (net (code "62") (name "unconnected-(J10-SBU1-PadA8)") (class "Default")
      (node (ref "J10") (pin "A8") (pinfunction "SBU1_A8") (pintype "passive"))
    )
    (net (code "63") (name "unconnected-(J10-SBU2-PadB8)") (class "Default")
      (node (ref "J10") (pin "B8") (pinfunction "SBU2_B8") (pintype "passive"))
    )
    (net (code "64") (name "unconnected-(J10-SSRXn1-PadB10)") (class "Default")
      (node (ref "J10") (pin "B10") (pinfunction "SSRXn1_B10") (pintype "passive"))
    )
    (net (code "65") (name "unconnected-(J10-SSRXn2-PadA10)") (class "Default")
      (node (ref "J10") (pin "A10") (pinfunction "SSRXn2_A10") (pintype "passive"))
    )
    (net (code "66") (name "unconnected-(J10-SSRXp1-PadB11)") (class "Default")
      (node (ref "J10") (pin "B11") (pinfunction "SSRXp1_B11") (pintype "passive"))
    )
    (net (code "67") (name "unconnected-(J10-SSRXp2-PadA11)") (class "Default")
      (node (ref "J10") (pin "A11") (pinfunction "SSRXp2_A11") (pintype "passive"))
    )
    (net (code "68") (name "unconnected-(J10-SSTXn1-PadA3)") (class "Default")
      (node (ref "J10") (pin "A3") (pinfunction "SSTXn1_A3") (pintype "passive"))
    )
    (net (code "69") (name "unconnected-(J10-SSTXn2-PadB3)") (class "Default")
      (node (ref "J10") (pin "B3") (pinfunction "SSTXn2_B3") (pintype "passive"))
    )
    (net (code "70") (name "unconnected-(J10-SSTXp1-PadA2)") (class "Default")
      (node (ref "J10") (pin "A2") (pinfunction "SSTXp1_A2") (pintype "passive"))
    )
    (net (code "71") (name "unconnected-(J10-SSTXp2-PadB2)") (class "Default")
      (node (ref "J10") (pin "B2") (pinfunction "SSTXp2_B2") (pintype "passive"))
    )
    (net (code "72") (name "unconnected-(J10-Shield-PadShell)") (class "Default")
      (node (ref "J10") (pin "Shell") (pinfunction "Shield_Shell") (pintype "passive"))
    )
    (net (code "73") (name "unconnected-(J14-PadMP1)") (class "Default")
      (node (ref "J14") (pin "MP1") (pinfunction "MP1_MP1") (pintype "passive+no_connect"))
    )
    (net (code "74") (name "unconnected-(J14-PadMP2)") (class "Default")
      (node (ref "J14") (pin "MP2") (pinfunction "MP2_MP2") (pintype "passive+no_connect"))
    )
    (net (code "75") (name "unconnected-(U4-NC-Pad2)") (class "Default")
      (node (ref "U4") (pin "2") (pinfunction "NC_2") (pintype "passive+no_connect"))
    )
    (net (code "76") (name "unconnected-(U4-NC-Pad3)") (class "Default")
      (node (ref "U4") (pin "3") (pinfunction "NC_3") (pintype "passive+no_connect"))
    )
    (net (code "77") (name "unconnected-(U5-ALERT-Pad3)") (class "Default")
      (node (ref "U5") (pin "3") (pinfunction "ALERT_3") (pintype "output+no_connect"))
    )
  )
)
